# LSM6DSO_ACCELERO.net
KiCad netlist of a schematic drawn in Altium Designer
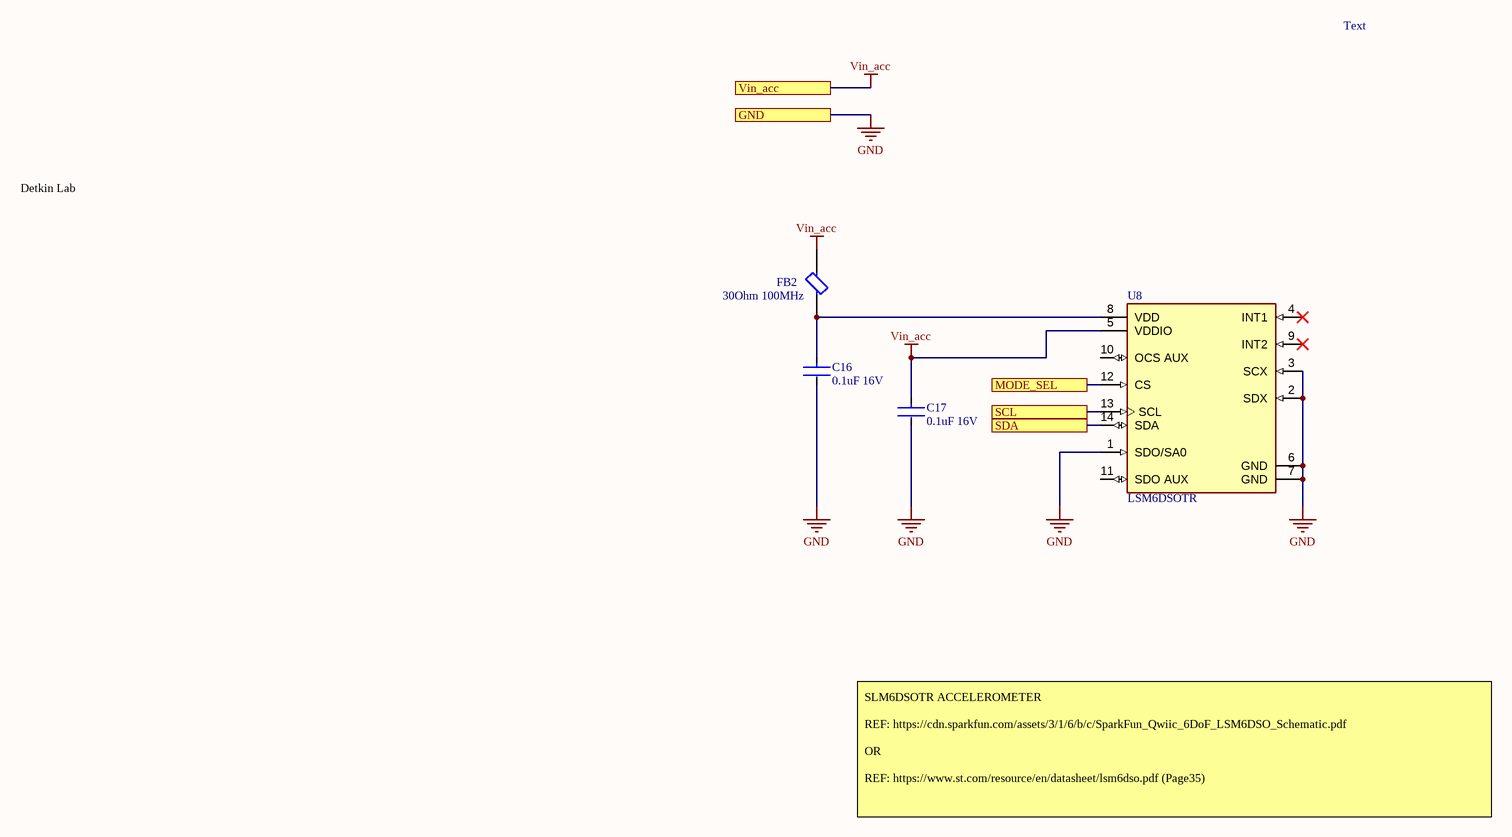
[diagram p0: LSM6DSO_ACCELERO.SchDoc]

(export (version "E")
  (design (tool "Eeschema 10.0.6"))
  (components
    (comp (ref "C16")
      (value "0.1uF 16V")
      (footprint "FP-CC0402-MFG")
      (description "CAP CER 0.1UF 16V X7R 0402")
      (fields (field (name "MANUFACTURER") "YAGEO") (field (name "TOLERANCE") "0.1"))
      (libsource (lib "Altium Content Vault") (part "11868f565c42a9108669ba33697ecf6"))
    )
    (comp (ref "C17")
      (value "0.1uF 16V")
      (footprint "FP-CC0402-MFG")
      (description "CAP CER 0.1UF 16V X7R 0402")
      (fields (field (name "MANUFACTURER") "YAGEO") (field (name "TOLERANCE") "0.1"))
      (libsource (lib "Altium Content Vault") (part "11868f565c42a9108669ba33697ecf6"))
    )
    (comp (ref "FB2")
      (value "30Ohm 100MHz")
      (footprint "FP-MPZ1608-MFG")
      (description "FERRITE BEAD 30 OHM 0603 1LN")
      (fields
        (field (name "MANUFACTURER") "TDK")
        (field (name "MANUFACTURER PART NUMBER") "MPZ1608S300ATAH0")
      )
      (libsource (lib "Altium Content Vault") (part "5f30dd21d616792df468990f7003faa"))
    )
    (comp (ref "U8")
      (value "LSM6DSOTR")
      (footprint "FP-LGA-14L-DM00249496-MFG")
      (description "INEMO INERTIAL MODULE: 3D ACCELE")
      (fields
        (field (name "OCTOPART") "https://octopart.com/lsm6dsotr-stmicroelectronics-81706672")
        (field (name "MANUFACTURER") "STMicroelectronics")
      )
      (libsource (lib "Altium Content Vault") (part "2908151a9596ea8f46216e3a0605c49"))
    )
  )
  (nets
    (net (code "1") (name "/MODE_SEL") (class "Default")
      (node (ref "U8") (pin "12") (pinfunction "CS_12") (pintype "input"))
    )
    (net (code "2") (name "/SCL") (class "Default")
      (node (ref "U8") (pin "13") (pinfunction "SCL_13") (pintype "input"))
    )
    (net (code "3") (name "/SDA") (class "Default")
      (node (ref "U8") (pin "14") (pinfunction "SDA_14") (pintype "bidirectional"))
    )
    (net (code "4") (name "GND") (class "Default")
      (node (ref "C16") (pin "2") (pinfunction "2_2") (pintype "passive"))
      (node (ref "C17") (pin "2") (pinfunction "2_2") (pintype "passive"))
      (node (ref "U8") (pin "1") (pinfunction "SDO/SA0_1") (pintype "input"))
      (node (ref "U8") (pin "2") (pinfunction "SDX_2") (pintype "input"))
      (node (ref "U8") (pin "3") (pinfunction "SCX_3") (pintype "input"))
      (node (ref "U8") (pin "6") (pinfunction "GND_6") (pintype "power_in"))
      (node (ref "U8") (pin "7") (pinfunction "GND_7") (pintype "power_in"))
    )
    (net (code "5") (name "Net-(U8-VDD)") (class "Default")
      (node (ref "C16") (pin "1") (pinfunction "1_1") (pintype "passive"))
      (node (ref "FB2") (pin "1") (pinfunction "1_1") (pintype "passive"))
      (node (ref "U8") (pin "8") (pinfunction "VDD_8") (pintype "power_in"))
    )
    (net (code "6") (name "Vin_acc") (class "Default")
      (node (ref "C17") (pin "1") (pinfunction "1_1") (pintype "passive"))
      (node (ref "FB2") (pin "2") (pinfunction "2_2") (pintype "passive"))
      (node (ref "U8") (pin "5") (pinfunction "VDDIO_5") (pintype "power_in"))
    )
    (net (code "7") (name "unconnected-(U8-INT1-Pad4)") (class "Default")
      (node (ref "U8") (pin "4") (pinfunction "INT1_4") (pintype "input+no_connect"))
    )
    (net (code "8") (name "unconnected-(U8-INT2-Pad9)") (class "Default")
      (node (ref "U8") (pin "9") (pinfunction "INT2_9") (pintype "input+no_connect"))
    )
    (net (code "9") (name "unconnected-(U8-OCS_AUX-Pad10)") (class "Default")
      (node (ref "U8") (pin "10") (pinfunction "OCS_AUX_10") (pintype "bidirectional"))
    )
    (net (code "10") (name "unconnected-(U8-SDO_AUX-Pad11)") (class "Default")
      (node (ref "U8") (pin "11") (pinfunction "SDO_AUX_11") (pintype "bidirectional"))
    )
  )
)
